# Sheet1.net
KiCad netlist of a schematic drawn in Altium Designer
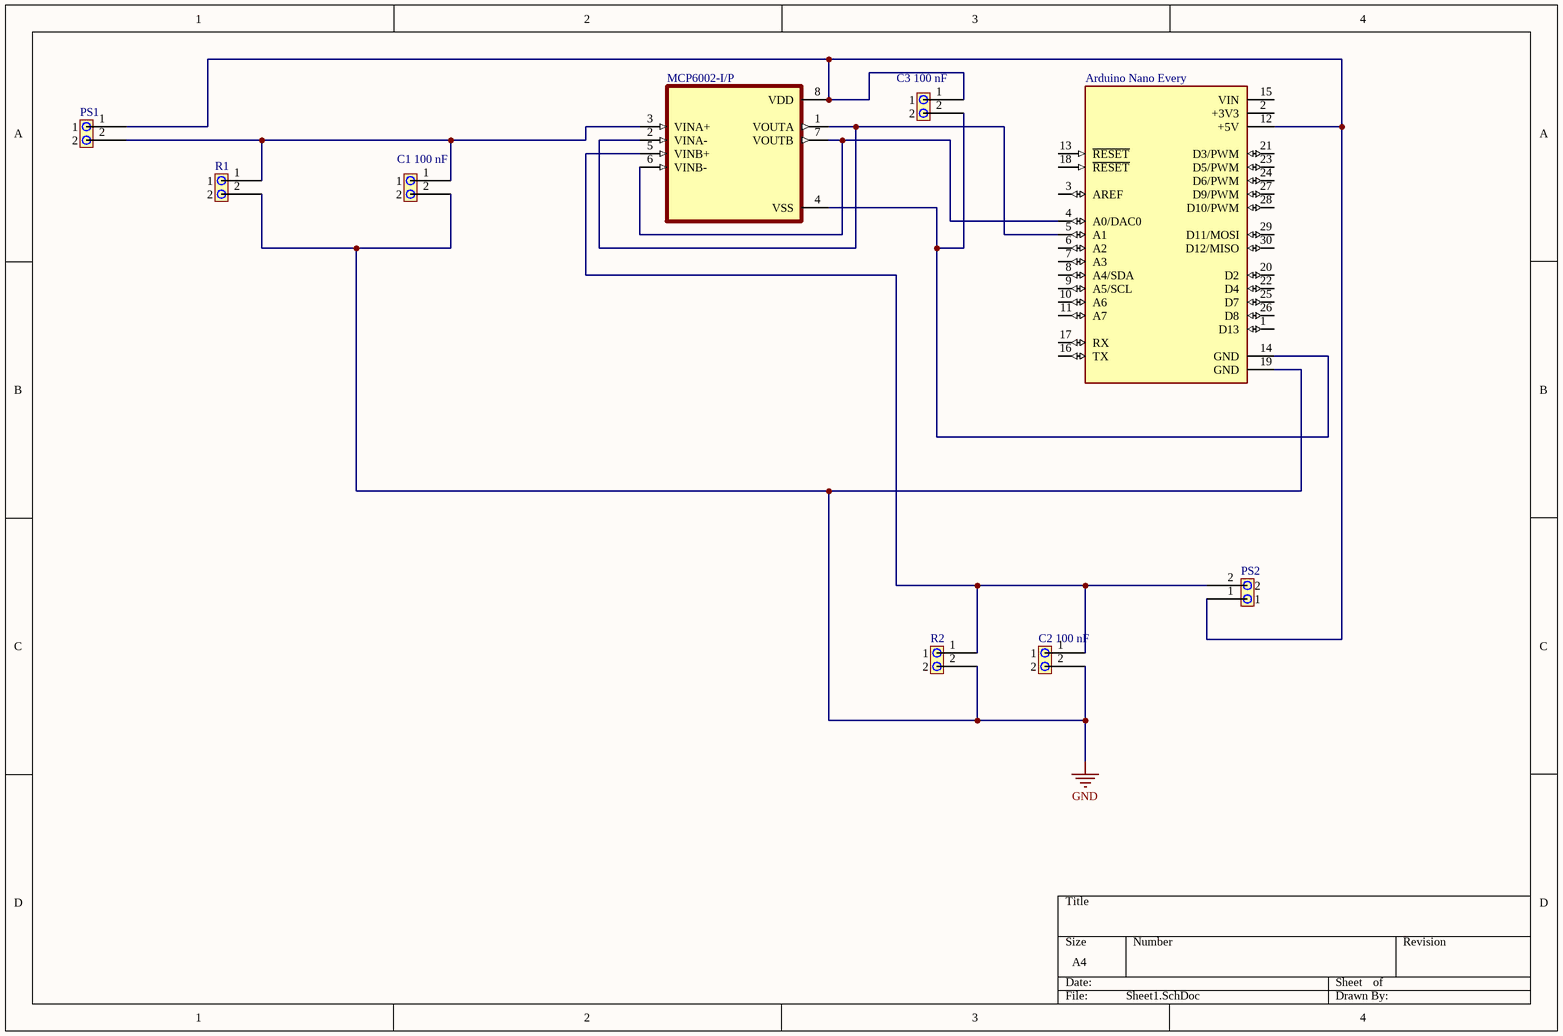
[diagram p0: Sheet1.SchDoc]

(export (version "E")
  (design (tool "Eeschema 10.0.6"))
  (components
    (comp (ref "Arduino Nano Every")
      (value "ABX00028")
      (footprint "MODULE_ABX00028")
      (description "Arduinoâ€™s 5V compatible board in the smallest available form factor: 45x18mm!")
      (fields (field (name "MF") "Arduino") (field (name "MP") "Arduino Nano Every"))
      (libsource (lib "UofE_SM_Group") (part "ABX00028"))
    )
    (comp (ref "C1 100 nF")
      (value "2 p female connector strainght 2.54 mm")
      (footprint "2 p female connector strainght  2.54 mm")
      (libsource (lib "") (part "2 p female connector strainght 2.54 mm_1"))
    )
    (comp (ref "C2 100 nF")
      (value "2 p female connector strainght 2.54 mm")
      (footprint "2 p female connector strainght  2.54 mm")
      (libsource (lib "") (part "2 p female connector strainght 2.54 mm_1"))
    )
    (comp (ref "C3 100 nF")
      (value "2 p female connector strainght 2.54 mm")
      (footprint "2 p female connector strainght  2.54 mm")
      (libsource (lib "") (part "2 p female connector strainght 2.54 mm_1"))
    )
    (comp (ref "MCP6002-I/P")
      (value "MCP6002-I/P")
      (footprint "DIP787W46P254L927H533Q8")
      (description "General Purpose Amplifier 2 Circuit Rail-to-Rail 8-PDIP")
      (fields (field (name "MF") "Microchip"))
      (libsource (lib "UofE_SM_Group") (part "MCP6002-I/P"))
    )
    (comp (ref "PS1")
      (value "2 p female connector strainght 2.54 mm")
      (footprint "2 p female connector strainght  2.54 mm")
      (libsource (lib "") (part "2 p female connector strainght 2.54 mm_1"))
    )
    (comp (ref "PS2")
      (value "2 p female connector strainght 2.54 mm")
      (footprint "2 p female connector strainght  2.54 mm")
      (libsource (lib "Schlib1") (part "2 p female connector strainght 2.54 mm"))
    )
    (comp (ref "R1")
      (value "2 p female connector strainght 2.54 mm")
      (footprint "2 p female connector strainght  2.54 mm")
      (libsource (lib "") (part "2 p female connector strainght 2.54 mm_1"))
    )
    (comp (ref "R2")
      (value "2 p female connector strainght 2.54 mm")
      (footprint "2 p female connector strainght  2.54 mm")
      (libsource (lib "") (part "2 p female connector strainght 2.54 mm_1"))
    )
  )
  (nets
    (net (code "1") (name "GND") (class "Default")
      (node (ref "Arduino Nano Every") (pin "19") (pinfunction "GND_19") (pintype "power_in"))
      (node (ref "C1 100 nF") (pin "2") (pinfunction "2_2") (pintype "passive"))
      (node (ref "C2 100 nF") (pin "2") (pinfunction "2_2") (pintype "passive"))
      (node (ref "R1") (pin "2") (pinfunction "2_2") (pintype "passive"))
      (node (ref "R2") (pin "2") (pinfunction "2_2") (pintype "passive"))
    )
    (net (code "2") (name "Net-(Arduino Nano Every-+5V)") (class "Default")
      (node (ref "Arduino Nano Every") (pin "12") (pinfunction "+5V_12") (pintype "power_in"))
      (node (ref "C3 100 nF") (pin "1") (pinfunction "1_1") (pintype "passive"))
      (node (ref "MCP6002-I/P") (pin "8") (pinfunction "VDD_8") (pintype "power_in"))
      (node (ref "PS1") (pin "1") (pinfunction "1_1") (pintype "passive"))
      (node (ref "PS2") (pin "1") (pinfunction "1_1") (pintype "passive"))
    )
    (net (code "3") (name "Net-(Arduino Nano Every-A0{slash}DAC0)") (class "Default")
      (node (ref "Arduino Nano Every") (pin "4") (pinfunction "A0/DAC0_4") (pintype "bidirectional"))
      (node (ref "MCP6002-I/P") (pin "6") (pinfunction "VINB-_6") (pintype "input"))
      (node (ref "MCP6002-I/P") (pin "7") (pinfunction "VOUTB_7") (pintype "output"))
    )
    (net (code "4") (name "Net-(Arduino Nano Every-A1)") (class "Default")
      (node (ref "Arduino Nano Every") (pin "5") (pinfunction "A1_5") (pintype "bidirectional"))
      (node (ref "MCP6002-I/P") (pin "1") (pinfunction "VOUTA_1") (pintype "output"))
      (node (ref "MCP6002-I/P") (pin "2") (pinfunction "VINA-_2") (pintype "input"))
    )
    (net (code "5") (name "Net-(MCP6002-I/P-VINA+)") (class "Default")
      (node (ref "C1 100 nF") (pin "1") (pinfunction "1_1") (pintype "passive"))
      (node (ref "MCP6002-I/P") (pin "3") (pinfunction "VINA+_3") (pintype "input"))
      (node (ref "PS1") (pin "2") (pinfunction "2_2") (pintype "passive"))
      (node (ref "R1") (pin "1") (pinfunction "1_1") (pintype "passive"))
    )
    (net (code "6") (name "Net-(MCP6002-I/P-VINB+)") (class "Default")
      (node (ref "C2 100 nF") (pin "1") (pinfunction "1_1") (pintype "passive"))
      (node (ref "MCP6002-I/P") (pin "5") (pinfunction "VINB+_5") (pintype "input"))
      (node (ref "PS2") (pin "2") (pinfunction "2_2") (pintype "passive"))
      (node (ref "R2") (pin "1") (pinfunction "1_1") (pintype "passive"))
    )
    (net (code "7") (name "Net-(MCP6002-I/P-VSS)") (class "Default")
      (node (ref "Arduino Nano Every") (pin "14") (pinfunction "GND_14") (pintype "power_in"))
      (node (ref "C3 100 nF") (pin "2") (pinfunction "2_2") (pintype "passive"))
      (node (ref "MCP6002-I/P") (pin "4") (pinfunction "VSS_4") (pintype "power_in"))
    )
    (net (code "8") (name "unconnected-(Arduino Nano Every-+3V3-Pad2)") (class "Default")
      (node (ref "Arduino Nano Every") (pin "2") (pinfunction "+3V3_2") (pintype "power_in"))
    )
    (net (code "9") (name "unconnected-(Arduino Nano Every-A2-Pad6)") (class "Default")
      (node (ref "Arduino Nano Every") (pin "6") (pinfunction "A2_6") (pintype "bidirectional"))
    )
    (net (code "10") (name "unconnected-(Arduino Nano Every-A3-Pad7)") (class "Default")
      (node (ref "Arduino Nano Every") (pin "7") (pinfunction "A3_7") (pintype "bidirectional"))
    )
    (net (code "11") (name "unconnected-(Arduino Nano Every-A4{slash}SDA-Pad8)") (class "Default")
      (node (ref "Arduino Nano Every") (pin "8") (pinfunction "A4/SDA_8") (pintype "bidirectional"))
    )
    (net (code "12") (name "unconnected-(Arduino Nano Every-A5{slash}SCL-Pad9)") (class "Default")
      (node (ref "Arduino Nano Every") (pin "9") (pinfunction "A5/SCL_9") (pintype "bidirectional"))
    )
    (net (code "13") (name "unconnected-(Arduino Nano Every-A6-Pad10)") (class "Default")
      (node (ref "Arduino Nano Every") (pin "10") (pinfunction "A6_10") (pintype "bidirectional"))
    )
    (net (code "14") (name "unconnected-(Arduino Nano Every-A7-Pad11)") (class "Default")
      (node (ref "Arduino Nano Every") (pin "11") (pinfunction "A7_11") (pintype "bidirectional"))
    )
    (net (code "15") (name "unconnected-(Arduino Nano Every-AREF-Pad3)") (class "Default")
      (node (ref "Arduino Nano Every") (pin "3") (pinfunction "AREF_3") (pintype "bidirectional"))
    )
    (net (code "16") (name "unconnected-(Arduino Nano Every-D2-Pad20)") (class "Default")
      (node (ref "Arduino Nano Every") (pin "20") (pinfunction "D2_20") (pintype "bidirectional"))
    )
    (net (code "17") (name "unconnected-(Arduino Nano Every-D3{slash}PWM-Pad21)") (class "Default")
      (node (ref "Arduino Nano Every") (pin "21") (pinfunction "D3/PWM_21") (pintype "bidirectional"))
    )
    (net (code "18") (name "unconnected-(Arduino Nano Every-D4-Pad22)") (class "Default")
      (node (ref "Arduino Nano Every") (pin "22") (pinfunction "D4_22") (pintype "bidirectional"))
    )
    (net (code "19") (name "unconnected-(Arduino Nano Every-D5{slash}PWM-Pad23)") (class "Default")
      (node (ref "Arduino Nano Every") (pin "23") (pinfunction "D5/PWM_23") (pintype "bidirectional"))
    )
    (net (code "20") (name "unconnected-(Arduino Nano Every-D6{slash}PWM-Pad24)") (class "Default")
      (node (ref "Arduino Nano Every") (pin "24") (pinfunction "D6/PWM_24") (pintype "bidirectional"))
    )
    (net (code "21") (name "unconnected-(Arduino Nano Every-D7-Pad25)") (class "Default")
      (node (ref "Arduino Nano Every") (pin "25") (pinfunction "D7_25") (pintype "bidirectional"))
    )
    (net (code "22") (name "unconnected-(Arduino Nano Every-D8-Pad26)") (class "Default")
      (node (ref "Arduino Nano Every") (pin "26") (pinfunction "D8_26") (pintype "bidirectional"))
    )
    (net (code "23") (name "unconnected-(Arduino Nano Every-D9{slash}PWM-Pad27)") (class "Default")
      (node (ref "Arduino Nano Every") (pin "27") (pinfunction "D9/PWM_27") (pintype "bidirectional"))
    )
    (net (code "24") (name "unconnected-(Arduino Nano Every-D10{slash}PWM-Pad28)") (class "Default")
      (node (ref "Arduino Nano Every") (pin "28") (pinfunction "D10/PWM_28") (pintype "bidirectional"))
    )
    (net (code "25") (name "unconnected-(Arduino Nano Every-D11{slash}MOSI-Pad29)") (class "Default")
      (node (ref "Arduino Nano Every") (pin "29") (pinfunction "D11/MOSI_29") (pintype "bidirectional"))
    )
    (net (code "26") (name "unconnected-(Arduino Nano Every-D12{slash}MISO-Pad30)") (class "Default")
      (node (ref "Arduino Nano Every") (pin "30") (pinfunction "D12/MISO_30") (pintype "bidirectional"))
    )
    (net (code "27") (name "unconnected-(Arduino Nano Every-D13-Pad1)") (class "Default")
      (node (ref "Arduino Nano Every") (pin "1") (pinfunction "D13_1") (pintype "bidirectional"))
    )
    (net (code "28") (name "unconnected-(Arduino Nano Every-RX-Pad17)") (class "Default")
      (node (ref "Arduino Nano Every") (pin "17") (pinfunction "RX_17") (pintype "bidirectional"))
    )
    (net (code "29") (name "unconnected-(Arduino Nano Every-TX-Pad16)") (class "Default")
      (node (ref "Arduino Nano Every") (pin "16") (pinfunction "TX_16") (pintype "bidirectional"))
    )
    (net (code "30") (name "unconnected-(Arduino Nano Every-VIN-Pad15)") (class "Default")
      (node (ref "Arduino Nano Every") (pin "15") (pinfunction "VIN_15") (pintype "power_in"))
    )
    (net (code "31") (name "unconnected-(Arduino Nano Every-~{RESET}-Pad13)") (class "Default")
      (node (ref "Arduino Nano Every") (pin "13") (pinfunction "~{RESET}_13") (pintype "input"))
    )
    (net (code "32") (name "unconnected-(Arduino Nano Every-~{RESET}-Pad18)") (class "Default")
      (node (ref "Arduino Nano Every") (pin "18") (pinfunction "~{RESET}_18") (pintype "input"))
    )
  )
)
